# PWM_fan_temperature_regulator.net
KiCad netlist of a schematic drawn in EasyEDA
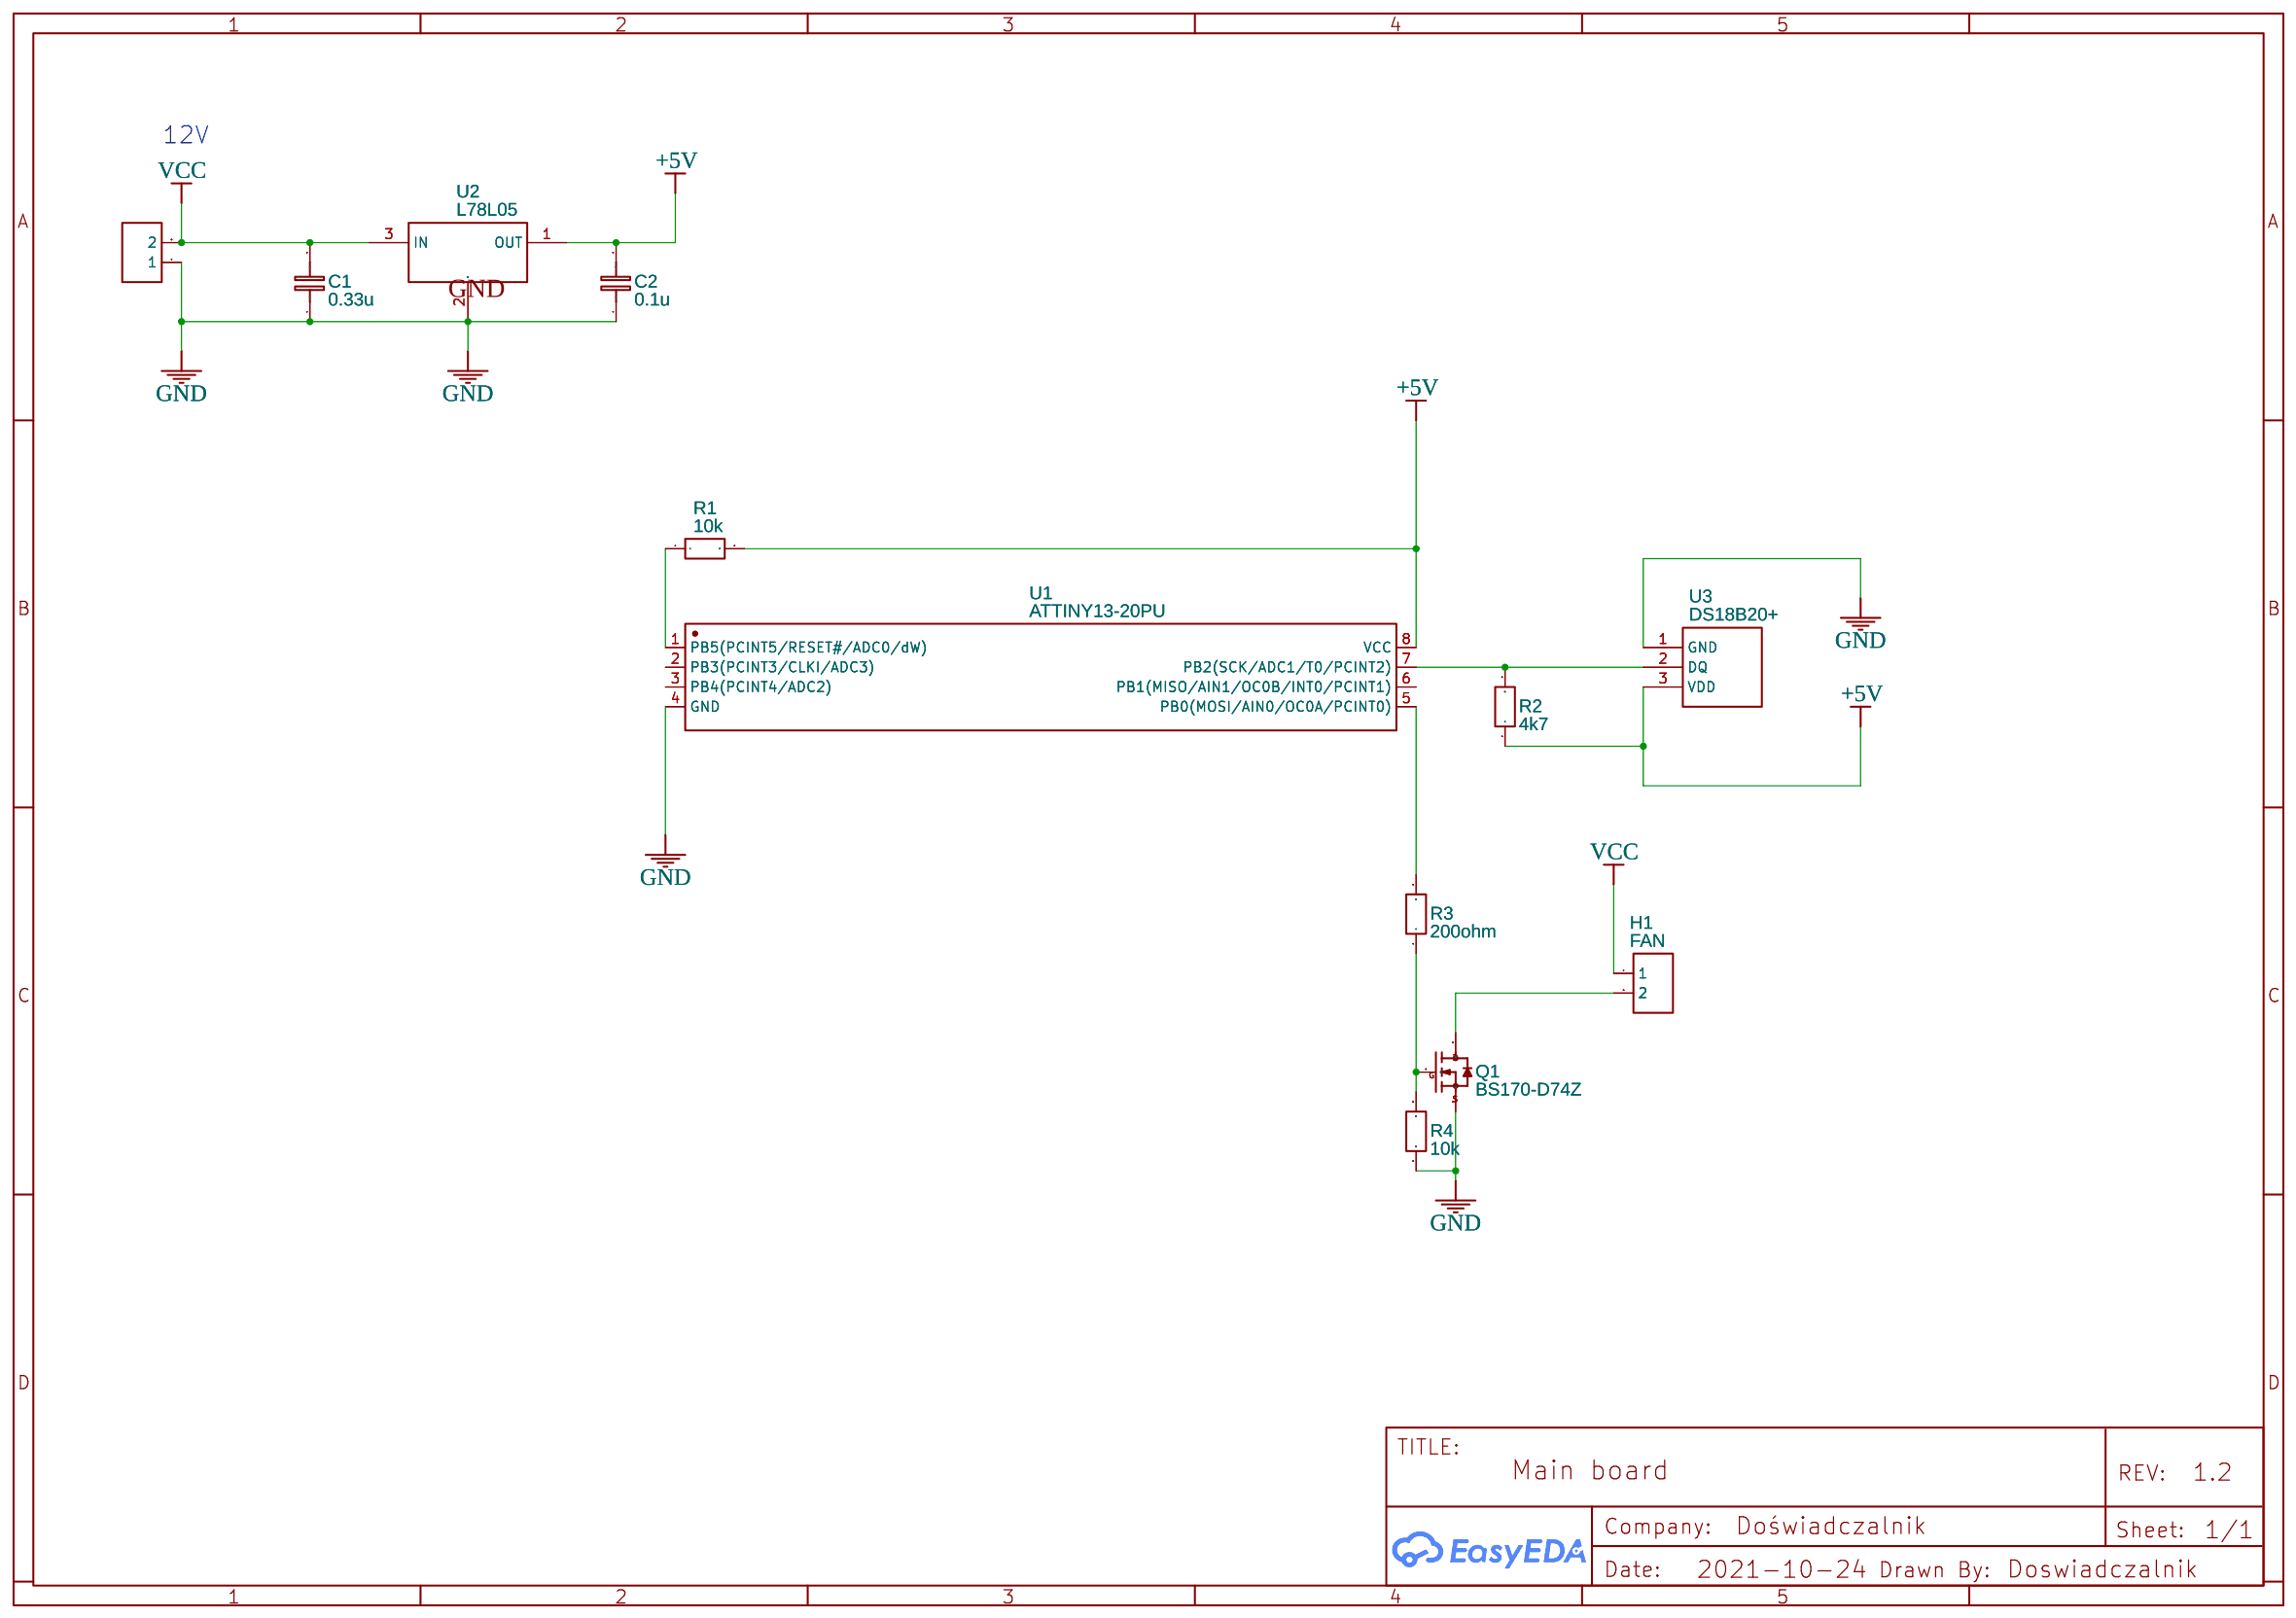
[diagram p0: schematic sheet]

(export (version "E")
  (design (tool "Eeschema 10.0.6"))
  (components
    (comp (ref "C1") (value "0.33u") (libsource (lib "") (part "C_0603_EU")))
    (comp (ref "C2") (value "0.1u") (libsource (lib "") (part "C_0603_EU")))
    (comp (ref "H1")
      (value "FAN")
      (fields (field (name "BOM_Supplier Part") "C49661"))
      (libsource (lib "") (part "HDR-F-2.54_1x2_1"))
    )
    (comp (ref "H2")
      (value "HDR-F-2.54_1x2")
      (fields (field (name "BOM_Supplier Part") "C49661"))
      (libsource (lib "") (part "HDR-F-2.54_1x2"))
    )
    (comp (ref "Q1")
      (value "BS170-D74Z")
      (fields (field (name "BOM_Supplier Part") "C900827"))
      (libsource (lib "") (part "BS170-D74Z"))
    )
    (comp (ref "R1") (value "10k") (libsource (lib "") (part "R_0603_EU")))
    (comp (ref "R2") (value "4k7") (libsource (lib "") (part "R_0603_EU_1")))
    (comp (ref "R3") (value "200ohm") (libsource (lib "") (part "R_0603_EU_1")))
    (comp (ref "R4") (value "10k") (libsource (lib "") (part "R_0603_EU_1")))
    (comp (ref "U1")
      (value "ATTINY13-20PU")
      (fields (field (name "BOM_Supplier Part") "C145757"))
      (libsource (lib "") (part "ATTINY13-20PU"))
    )
    (comp (ref "U2")
      (value "L78L05")
      (fields
        (field (name "BOM_Manufacturer Part") "L78L05ACZTR")
        (field (name "BOM_Supplier Part") "C118270")
      )
      (libsource (lib "") (part "L78L05ACZTR"))
    )
    (comp (ref "U3")
      (value "DS18B20+")
      (fields (field (name "BOM_Supplier Part") "C9753"))
      (libsource (lib "") (part "DS18B20+"))
    )
  )
  (nets
    (net (code "1") (name "+5V") (class "Default")
      (node (ref "C2") (pin "2") (pinfunction "2_2") (pintype "unspecified"))
      (node (ref "R1") (pin "2") (pinfunction "2_2") (pintype "unspecified"))
      (node (ref "R2") (pin "1") (pinfunction "1_1") (pintype "unspecified"))
      (node (ref "U1") (pin "8") (pinfunction "VCC_8") (pintype "unspecified"))
      (node (ref "U2") (pin "1") (pinfunction "OUT_1") (pintype "passive"))
      (node (ref "U3") (pin "3") (pinfunction "VDD_3") (pintype "unspecified"))
    )
    (net (code "2") (name "GND") (class "Default")
      (node (ref "C1") (pin "1") (pinfunction "1_1") (pintype "unspecified"))
      (node (ref "C2") (pin "1") (pinfunction "1_1") (pintype "unspecified"))
      (node (ref "H2") (pin "1") (pinfunction "1_1") (pintype "input"))
      (node (ref "Q1") (pin "3") (pinfunction "S_3") (pintype "unspecified"))
      (node (ref "R4") (pin "1") (pinfunction "1_1") (pintype "unspecified"))
      (node (ref "U1") (pin "4") (pinfunction "GND_4") (pintype "unspecified"))
      (node (ref "U2") (pin "2") (pinfunction "GND_2") (pintype "passive"))
      (node (ref "U3") (pin "1") (pinfunction "GND_1") (pintype "unspecified"))
    )
    (net (code "3") (name "Net-(Q1-D)") (class "Default")
      (node (ref "H1") (pin "2") (pinfunction "2_2") (pintype "input"))
      (node (ref "Q1") (pin "1") (pinfunction "D_1") (pintype "unspecified"))
    )
    (net (code "4") (name "Net-(Q1-G)") (class "Default")
      (node (ref "Q1") (pin "2") (pinfunction "G_2") (pintype "unspecified"))
      (node (ref "R3") (pin "1") (pinfunction "1_1") (pintype "unspecified"))
      (node (ref "R4") (pin "2") (pinfunction "2_2") (pintype "unspecified"))
    )
    (net (code "5") (name "Net-(U1-PB0(MOSI{slash}AIN0{slash}OC0A{slash}PCINT0))") (class "Default")
      (node (ref "R3") (pin "2") (pinfunction "2_2") (pintype "unspecified"))
      (node (ref "U1") (pin "5") (pinfunction "PB0(MOSI/AIN0/OC0A/PCINT0)_5") (pintype "unspecified"))
    )
    (net (code "6") (name "Net-(U1-PB2(SCK{slash}ADC1{slash}T0{slash}PCINT2))") (class "Default")
      (node (ref "R2") (pin "2") (pinfunction "2_2") (pintype "unspecified"))
      (node (ref "U1") (pin "7") (pinfunction "PB2(SCK/ADC1/T0/PCINT2)_7") (pintype "unspecified"))
      (node (ref "U3") (pin "2") (pinfunction "DQ_2") (pintype "unspecified"))
    )
    (net (code "7") (name "Net-(U1-PB5(PCINT5{slash}RESET#{slash}ADC0{slash}dW))") (class "Default")
      (node (ref "R1") (pin "1") (pinfunction "1_1") (pintype "unspecified"))
      (node (ref "U1") (pin "1") (pinfunction "PB5(PCINT5/RESET#/ADC0/dW)_1") (pintype "unspecified"))
    )
    (net (code "8") (name "VCC") (class "Default")
      (node (ref "C1") (pin "2") (pinfunction "2_2") (pintype "unspecified"))
      (node (ref "H1") (pin "1") (pinfunction "1_1") (pintype "input"))
      (node (ref "H2") (pin "2") (pinfunction "2_2") (pintype "input"))
      (node (ref "U2") (pin "3") (pinfunction "IN_3") (pintype "passive"))
    )
    (net (code "9") (name "unconnected-(U1-PB1(MISO{slash}AIN1{slash}OC0B{slash}INT0{slash}PCINT1)-Pad6)") (class "Default")
      (node (ref "U1") (pin "6") (pinfunction "PB1(MISO/AIN1/OC0B/INT0/PCINT1)_6") (pintype "unspecified"))
    )
    (net (code "10") (name "unconnected-(U1-PB3(PCINT3{slash}CLKI{slash}ADC3)-Pad2)") (class "Default")
      (node (ref "U1") (pin "2") (pinfunction "PB3(PCINT3/CLKI/ADC3)_2") (pintype "unspecified"))
    )
    (net (code "11") (name "unconnected-(U1-PB4(PCINT4{slash}ADC2)-Pad3)") (class "Default")
      (node (ref "U1") (pin "3") (pinfunction "PB4(PCINT4/ADC2)_3") (pintype "unspecified"))
    )
  )
)
